# oldARK.net
KiCad netlist of a schematic drawn in EAGLE
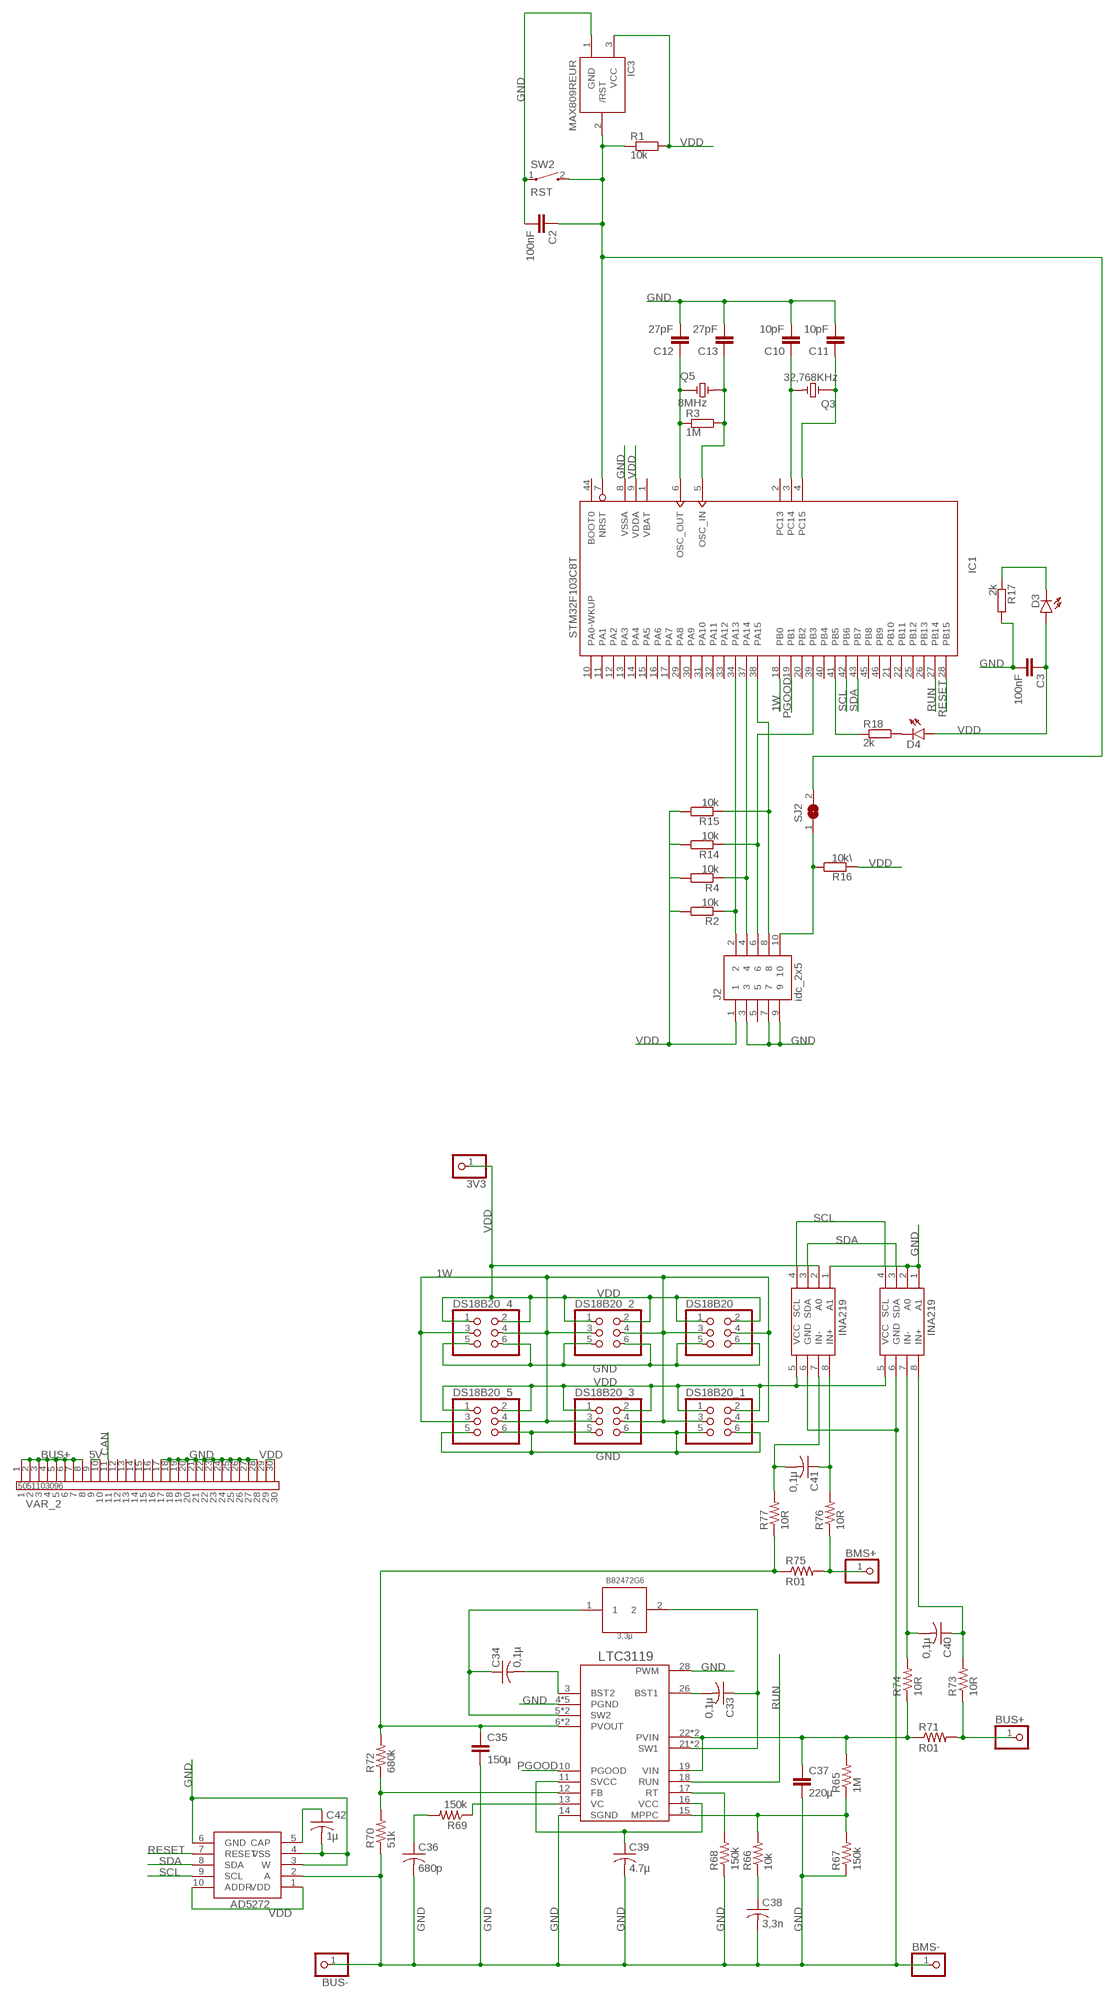
[diagram p0: schematic, sheet 1]

(export (version "E")
  (design (tool "Eeschema 10.0.6"))
  (components
    (comp (ref "3,3µH")
      (value "3,3µ")
      (footprint "eagle-import:B82472G6")
      (libsource (lib "eagle-import") (part "B82472G6"))
    )
    (comp (ref "3V3")
      (value "PINHD-1X1")
      (footprint "eagle-import:1X01")
      (libsource (lib "eagle-import") (part "PINHD-1X1"))
    )
    (comp (ref "BMS+")
      (value "PINHD-1X1")
      (footprint "eagle-import:1X01")
      (libsource (lib "eagle-import") (part "PINHD-1X1"))
    )
    (comp (ref "BMS-")
      (value "PINHD-1X1")
      (footprint "eagle-import:1X01")
      (libsource (lib "eagle-import") (part "PINHD-1X1"))
    )
    (comp (ref "BUS+")
      (value "PINHD-1X1")
      (footprint "eagle-import:1X01")
      (libsource (lib "eagle-import") (part "PINHD-1X1"))
    )
    (comp (ref "BUS-")
      (value "PINHD-1X1")
      (footprint "eagle-import:1X01")
      (libsource (lib "eagle-import") (part "PINHD-1X1"))
    )
    (comp (ref "C2")
      (value "100nF")
      (footprint "eagle-import:C0603")
      (libsource (lib "eagle-import") (part "C-EUC0603"))
    )
    (comp (ref "C3")
      (value "100nF")
      (footprint "eagle-import:C0603")
      (libsource (lib "eagle-import") (part "C-EUC0603"))
    )
    (comp (ref "C10")
      (value "10pF")
      (footprint "eagle-import:C0603")
      (libsource (lib "eagle-import") (part "C-EUC0603"))
    )
    (comp (ref "C11")
      (value "10pF")
      (footprint "eagle-import:C0603")
      (libsource (lib "eagle-import") (part "C-EUC0603"))
    )
    (comp (ref "C12")
      (value "27pF")
      (footprint "eagle-import:C0603")
      (libsource (lib "eagle-import") (part "C-EUC0603"))
    )
    (comp (ref "C13")
      (value "27pF")
      (footprint "eagle-import:C0603")
      (libsource (lib "eagle-import") (part "C-EUC0603"))
    )
    (comp (ref "C33")
      (value "0,1µ")
      (footprint "eagle-import:C0603")
      (libsource (lib "eagle-import") (part "C-USC0603"))
    )
    (comp (ref "C34")
      (value "0,1µ")
      (footprint "eagle-import:C0603")
      (libsource (lib "eagle-import") (part "C-USC0603"))
    )
    (comp (ref "C35")
      (value "150µ")
      (footprint "eagle-import:ECAP150")
      (libsource (lib "eagle-import") (part "ECAPECAP150"))
    )
    (comp (ref "C36")
      (value "680p")
      (footprint "eagle-import:C1206")
      (libsource (lib "eagle-import") (part "C-USC1206"))
    )
    (comp (ref "C37")
      (value "220µ")
      (footprint "eagle-import:ECAP220")
      (libsource (lib "eagle-import") (part "ECAPECAP220"))
    )
    (comp (ref "C38")
      (value "3,3n")
      (footprint "eagle-import:C1206")
      (libsource (lib "eagle-import") (part "C-USC1206"))
    )
    (comp (ref "C39")
      (value "4.7µ")
      (footprint "eagle-import:C1206")
      (libsource (lib "eagle-import") (part "C-USC1206"))
    )
    (comp (ref "C40")
      (value "0,1µ")
      (footprint "eagle-import:C0603")
      (libsource (lib "eagle-import") (part "C-USC0603"))
    )
    (comp (ref "C41")
      (value "0,1µ")
      (footprint "eagle-import:C0603")
      (libsource (lib "eagle-import") (part "C-USC0603"))
    )
    (comp (ref "C42")
      (value "1µ")
      (footprint "eagle-import:C0603")
      (libsource (lib "eagle-import") (part "C-USC0603"))
    )
    (comp (ref "D3")
      (value "HLMP6")
      (footprint "eagle-import:HLMP6")
      (fields (field (name "MF") "AGILENT TECHNOLOGIES") (field (name "MPN") "HLMP-6500"))
      (libsource (lib "eagle-import") (part "HLMP6"))
    )
    (comp (ref "D4")
      (value "HLMP6")
      (footprint "eagle-import:HLMP6")
      (fields (field (name "MF") "AGILENT TECHNOLOGIES") (field (name "MPN") "HLMP-6500"))
      (libsource (lib "eagle-import") (part "HLMP6"))
    )
    (comp (ref "DS18B20")
      (value "PINHD-2X3M")
      (footprint "eagle-import:2X03M")
      (libsource (lib "eagle-import") (part "PINHD-2X3M"))
    )
    (comp (ref "DS18B20_1")
      (value "PINHD-2X3M")
      (footprint "eagle-import:2X03M")
      (libsource (lib "eagle-import") (part "PINHD-2X3M"))
    )
    (comp (ref "DS18B20_2")
      (value "PINHD-2X3M")
      (footprint "eagle-import:2X03M")
      (libsource (lib "eagle-import") (part "PINHD-2X3M"))
    )
    (comp (ref "DS18B20_3")
      (value "PINHD-2X3M")
      (footprint "eagle-import:2X03M")
      (libsource (lib "eagle-import") (part "PINHD-2X3M"))
    )
    (comp (ref "DS18B20_4")
      (value "PINHD-2X3M")
      (footprint "eagle-import:2X03M")
      (libsource (lib "eagle-import") (part "PINHD-2X3M"))
    )
    (comp (ref "DS18B20_5")
      (value "PINHD-2X3M")
      (footprint "eagle-import:2X03M")
      (libsource (lib "eagle-import") (part "PINHD-2X3M"))
    )
    (comp (ref "IC1")
      (value "STM32F103C8T")
      (footprint "eagle-import:LQFP48")
      (libsource (lib "eagle-import") (part "STM32F103CT8"))
    )
    (comp (ref "IC3")
      (value "MAX809REUR")
      (footprint "eagle-import:SOT23")
      (fields (field (name "MF") "ON Semiconductor") (field (name "MP") "MAX809"))
      (libsource (lib "eagle-import") (part "MAX809EUR"))
    )
    (comp (ref "J2")
      (value "idc_2x5")
      (footprint "eagle-import:CNC_3221-10-0100-00")
      (fields (field (name "MF") "CNC Tech") (field (name "MP") "3221-10-0100-00"))
      (libsource (lib "eagle-import") (part "3221-10-0100-00"))
    )
    (comp (ref "Q3")
      (value "32,768KHz")
      (footprint "eagle-import:XTAL_9C-8.000MEEJ-T")
      (fields (field (name "MF") "TXC CORPORATION") (field (name "MP") "9C-8.000MEEJ-T"))
      (libsource (lib "eagle-import") (part "9C-8.000MEEJ-T"))
    )
    (comp (ref "Q5")
      (value "8MHz")
      (footprint "eagle-import:XTAL_9C-8.000MEEJ-T")
      (fields (field (name "MF") "TXC CORPORATION") (field (name "MP") "9C-8.000MEEJ-T"))
      (libsource (lib "eagle-import") (part "9C-8.000MEEJ-T"))
    )
    (comp (ref "R1")
      (value "10k")
      (footprint "eagle-import:BVS")
      (libsource (lib "eagle-import") (part "BVS"))
    )
    (comp (ref "R2")
      (value "10k")
      (footprint "eagle-import:BVS")
      (libsource (lib "eagle-import") (part "BVS"))
    )
    (comp (ref "R3")
      (value "1M")
      (footprint "eagle-import:BVS")
      (libsource (lib "eagle-import") (part "BVS"))
    )
    (comp (ref "R4")
      (value "10k")
      (footprint "eagle-import:BVS")
      (libsource (lib "eagle-import") (part "BVS"))
    )
    (comp (ref "R14")
      (value "10k")
      (footprint "eagle-import:BVS")
      (libsource (lib "eagle-import") (part "BVS"))
    )
    (comp (ref "R15")
      (value "10k")
      (footprint "eagle-import:BVS")
      (libsource (lib "eagle-import") (part "BVS"))
    )
    (comp (ref "R16")
      (value "10k\\")
      (footprint "eagle-import:BVS")
      (libsource (lib "eagle-import") (part "BVS"))
    )
    (comp (ref "R17")
      (value "2k")
      (footprint "eagle-import:BVS")
      (libsource (lib "eagle-import") (part "BVS"))
    )
    (comp (ref "R18")
      (value "2k")
      (footprint "eagle-import:BVS")
      (libsource (lib "eagle-import") (part "BVS"))
    )
    (comp (ref "R65")
      (value "1M")
      (footprint "eagle-import:R0603")
      (libsource (lib "eagle-import") (part "resistor_348_R-US_R0603"))
    )
    (comp (ref "R66")
      (value "10k")
      (footprint "eagle-import:R0603")
      (libsource (lib "eagle-import") (part "resistor_348_R-US_R0603"))
    )
    (comp (ref "R67")
      (value "150k")
      (footprint "eagle-import:R0603")
      (libsource (lib "eagle-import") (part "resistor_348_R-US_R0603"))
    )
    (comp (ref "R68")
      (value "150k")
      (footprint "eagle-import:R0603")
      (libsource (lib "eagle-import") (part "resistor_348_R-US_R0603"))
    )
    (comp (ref "R69")
      (value "150k")
      (footprint "eagle-import:R0603")
      (libsource (lib "eagle-import") (part "resistor_348_R-US_R0603"))
    )
    (comp (ref "R70")
      (value "51k")
      (footprint "eagle-import:R0603")
      (libsource (lib "eagle-import") (part "resistor_348_R-US_R0603"))
    )
    (comp (ref "R71")
      (value "R01")
      (footprint "eagle-import:R2512")
      (libsource (lib "eagle-import") (part "R-US_R2512"))
    )
    (comp (ref "R72")
      (value "680k")
      (footprint "eagle-import:R0603")
      (libsource (lib "eagle-import") (part "resistor_348_R-US_R0603"))
    )
    (comp (ref "R73")
      (value "10R")
      (footprint "eagle-import:R0603")
      (libsource (lib "eagle-import") (part "resistor_348_R-US_R0603"))
    )
    (comp (ref "R74")
      (value "10R")
      (footprint "eagle-import:R0603")
      (libsource (lib "eagle-import") (part "resistor_348_R-US_R0603"))
    )
    (comp (ref "R75")
      (value "R01")
      (footprint "eagle-import:R2512")
      (libsource (lib "eagle-import") (part "R-US_R2512"))
    )
    (comp (ref "R76")
      (value "10R")
      (footprint "eagle-import:R0603")
      (libsource (lib "eagle-import") (part "resistor_348_R-US_R0603"))
    )
    (comp (ref "R77")
      (value "10R")
      (footprint "eagle-import:R0603")
      (libsource (lib "eagle-import") (part "resistor_348_R-US_R0603"))
    )
    (comp (ref "SJ2")
      (value "SJW")
      (footprint "eagle-import:SJW")
      (libsource (lib "eagle-import") (part "SJW"))
    )
    (comp (ref "SW2")
      (value "RST")
      (footprint "eagle-import:SW_1437566-3")
      (fields (field (name "COMMENT") "1437566-3") (field (name "MF") "TE Connectivity"))
      (libsource (lib "eagle-import") (part "1437566-3"))
    )
    (comp (ref "U$4")
      (value "5051103096")
      (footprint "eagle-import:5051103096")
      (libsource (lib "eagle-import") (part "5051103096"))
    )
    (comp (ref "U$57")
      (value "INA219AID")
      (footprint "eagle-import:INA219AID")
      (libsource (lib "eagle-import") (part "INA219AID"))
    )
    (comp (ref "U$58")
      (value "INA219AID")
      (footprint "eagle-import:INA219AID")
      (libsource (lib "eagle-import") (part "INA219AID"))
    )
    (comp (ref "U$59")
      (value "LTC3119")
      (footprint "eagle-import:LTC3119")
      (libsource (lib "eagle-import") (part "LTC3119"))
    )
    (comp (ref "U$60")
      (value "AD5272")
      (footprint "eagle-import:AD5272")
      (libsource (lib "eagle-import") (part "AD5272"))
    )
  )
  (nets
    (net (code "1") (name "/1W") (class "Default")
      (node (ref "DS18B20") (pin "3") (pinfunction "3_3") (pintype "passive"))
      (node (ref "DS18B20") (pin "4") (pinfunction "4_4") (pintype "passive"))
      (node (ref "DS18B20_1") (pin "3") (pinfunction "3_3") (pintype "passive"))
      (node (ref "DS18B20_1") (pin "4") (pinfunction "4_4") (pintype "passive"))
      (node (ref "DS18B20_2") (pin "3") (pinfunction "3_3") (pintype "passive"))
      (node (ref "DS18B20_2") (pin "4") (pinfunction "4_4") (pintype "passive"))
      (node (ref "DS18B20_3") (pin "3") (pinfunction "3_3") (pintype "passive"))
      (node (ref "DS18B20_3") (pin "4") (pinfunction "4_4") (pintype "passive"))
      (node (ref "DS18B20_4") (pin "3") (pinfunction "3_3") (pintype "passive"))
      (node (ref "DS18B20_4") (pin "4") (pinfunction "4_4") (pintype "passive"))
      (node (ref "DS18B20_5") (pin "3") (pinfunction "3_3") (pintype "passive"))
      (node (ref "DS18B20_5") (pin "4") (pinfunction "4_4") (pintype "passive"))
      (node (ref "IC1") (pin "18") (pinfunction "PB0_18") (pintype "bidirectional"))
    )
    (net (code "2") (name "/5V") (class "Default")
      (node (ref "U$4") (pin "10") (pinfunction "10_10") (pintype "bidirectional"))
      (node (ref "U$4") (pin "9") (pinfunction "9_9") (pintype "bidirectional"))
    )
    (net (code "3") (name "/BUS+") (class "Default")
      (node (ref "U$4") (pin "1") (pinfunction "1_1") (pintype "bidirectional"))
      (node (ref "U$4") (pin "2") (pinfunction "2_2") (pintype "bidirectional"))
      (node (ref "U$4") (pin "3") (pinfunction "3_3") (pintype "bidirectional"))
      (node (ref "U$4") (pin "4") (pinfunction "4_4") (pintype "bidirectional"))
      (node (ref "U$4") (pin "5") (pinfunction "5_5") (pintype "bidirectional"))
      (node (ref "U$4") (pin "6") (pinfunction "6_6") (pintype "bidirectional"))
      (node (ref "U$4") (pin "7") (pinfunction "7_7") (pintype "bidirectional"))
      (node (ref "U$4") (pin "8") (pinfunction "8_8") (pintype "bidirectional"))
    )
    (net (code "5") (name "/GND") (class "Default")
      (node (ref "BMS-") (pin "1") (pinfunction "1_1") (pintype "passive"))
      (node (ref "BUS-") (pin "1") (pinfunction "1_1") (pintype "passive"))
      (node (ref "C10") (pin "2") (pinfunction "2_2") (pintype "passive"))
      (node (ref "C11") (pin "2") (pinfunction "2_2") (pintype "passive"))
      (node (ref "C12") (pin "2") (pinfunction "2_2") (pintype "passive"))
      (node (ref "C13") (pin "2") (pinfunction "2_2") (pintype "passive"))
      (node (ref "C2") (pin "2") (pinfunction "2_2") (pintype "passive"))
      (node (ref "C3") (pin "2") (pinfunction "2_2") (pintype "passive"))
      (node (ref "C35") (pin "P$2") (pinfunction "2_P$2") (pintype "passive"))
      (node (ref "C36") (pin "2") (pinfunction "2_2") (pintype "passive"))
      (node (ref "C37") (pin "P$2") (pinfunction "2_P$2") (pintype "passive"))
      (node (ref "C38") (pin "2") (pinfunction "2_2") (pintype "passive"))
      (node (ref "C39") (pin "2") (pinfunction "2_2") (pintype "passive"))
      (node (ref "C42") (pin "2") (pinfunction "2_2") (pintype "passive"))
      (node (ref "DS18B20") (pin "5") (pinfunction "5_5") (pintype "passive"))
      (node (ref "DS18B20") (pin "6") (pinfunction "6_6") (pintype "passive"))
      (node (ref "DS18B20_1") (pin "5") (pinfunction "5_5") (pintype "passive"))
      (node (ref "DS18B20_1") (pin "6") (pinfunction "6_6") (pintype "passive"))
      (node (ref "DS18B20_2") (pin "5") (pinfunction "5_5") (pintype "passive"))
      (node (ref "DS18B20_2") (pin "6") (pinfunction "6_6") (pintype "passive"))
      (node (ref "DS18B20_3") (pin "5") (pinfunction "5_5") (pintype "passive"))
      (node (ref "DS18B20_3") (pin "6") (pinfunction "6_6") (pintype "passive"))
      (node (ref "DS18B20_4") (pin "5") (pinfunction "5_5") (pintype "passive"))
      (node (ref "DS18B20_4") (pin "6") (pinfunction "6_6") (pintype "passive"))
      (node (ref "DS18B20_5") (pin "5") (pinfunction "5_5") (pintype "passive"))
      (node (ref "DS18B20_5") (pin "6") (pinfunction "6_6") (pintype "passive"))
      (node (ref "IC1") (pin "8") (pinfunction "VSSA_8") (pintype "power_in"))
      (node (ref "IC3") (pin "1") (pinfunction "GND_1") (pintype "power_in"))
      (node (ref "J2") (pin "3") (pinfunction "3_3") (pintype "passive"))
      (node (ref "J2") (pin "7") (pinfunction "7_7") (pintype "passive"))
      (node (ref "J2") (pin "9") (pinfunction "9_9") (pintype "passive"))
      (node (ref "R17") (pin "1") (pinfunction "1_1") (pintype "passive"))
      (node (ref "R67") (pin "1") (pinfunction "1_1") (pintype "passive"))
      (node (ref "R68") (pin "1") (pinfunction "1_1") (pintype "passive"))
      (node (ref "R70") (pin "1") (pinfunction "1_1") (pintype "passive"))
      (node (ref "SW2") (pin "1") (pinfunction "1_1") (pintype "passive"))
      (node (ref "U$4") (pin "17") (pinfunction "17_17") (pintype "bidirectional"))
      (node (ref "U$4") (pin "18") (pinfunction "18_18") (pintype "bidirectional"))
      (node (ref "U$4") (pin "19") (pinfunction "19_19") (pintype "bidirectional"))
      (node (ref "U$4") (pin "20") (pinfunction "20_20") (pintype "bidirectional"))
      (node (ref "U$4") (pin "21") (pinfunction "21_21") (pintype "bidirectional"))
      (node (ref "U$4") (pin "22") (pinfunction "22_22") (pintype "bidirectional"))
      (node (ref "U$4") (pin "23") (pinfunction "23_23") (pintype "bidirectional"))
      (node (ref "U$4") (pin "24") (pinfunction "24_24") (pintype "bidirectional"))
      (node (ref "U$4") (pin "25") (pinfunction "25_25") (pintype "bidirectional"))
      (node (ref "U$4") (pin "26") (pinfunction "26_26") (pintype "bidirectional"))
      (node (ref "U$4") (pin "27") (pinfunction "27_27") (pintype "bidirectional"))
      (node (ref "U$4") (pin "28") (pinfunction "28_28") (pintype "bidirectional"))
      (node (ref "U$57") (pin "1") (pinfunction "A1_1") (pintype "bidirectional"))
      (node (ref "U$57") (pin "6") (pinfunction "GND_6") (pintype "bidirectional"))
      (node (ref "U$58") (pin "1") (pinfunction "A1_1") (pintype "bidirectional"))
      (node (ref "U$58") (pin "2") (pinfunction "A0_2") (pintype "bidirectional"))
      (node (ref "U$58") (pin "6") (pinfunction "GND_6") (pintype "bidirectional"))
      (node (ref "U$59") (pin "14") (pinfunction "SGND_14") (pintype "bidirectional"))
      (node (ref "U$59") (pin "20") (pinfunction "PGND_20") (pintype "bidirectional"))
      (node (ref "U$59") (pin "25") (pinfunction "PGND_25") (pintype "bidirectional"))
      (node (ref "U$59") (pin "28") (pinfunction "PWM_28") (pintype "bidirectional"))
      (node (ref "U$59") (pin "29") (pinfunction "PGND_29") (pintype "bidirectional"))
      (node (ref "U$59") (pin "4") (pinfunction "PGND_4") (pintype "bidirectional"))
      (node (ref "U$59") (pin "9") (pinfunction "PGND_9") (pintype "bidirectional"))
      (node (ref "U$60") (pin "2") (pinfunction "A_2") (pintype "bidirectional"))
      (node (ref "U$60") (pin "3") (pinfunction "W_3") (pintype "bidirectional"))
      (node (ref "U$60") (pin "4") (pinfunction "VSS_4") (pintype "bidirectional"))
      (node (ref "U$60") (pin "6") (pinfunction "GND_6") (pintype "bidirectional"))
    )
    (net (code "6") (name "/PGOOD") (class "Default")
      (node (ref "IC1") (pin "19") (pinfunction "PB1_19") (pintype "bidirectional"))
      (node (ref "U$59") (pin "10") (pinfunction "PGOOD_10") (pintype "bidirectional"))
    )
    (net (code "7") (name "/RESET") (class "Default")
      (node (ref "IC1") (pin "28") (pinfunction "PB15_28") (pintype "bidirectional"))
      (node (ref "U$60") (pin "7") (pinfunction "RESET_7") (pintype "bidirectional"))
    )
    (net (code "8") (name "/RUN") (class "Default")
      (node (ref "IC1") (pin "27") (pinfunction "PB14_27") (pintype "bidirectional"))
      (node (ref "U$59") (pin "18") (pinfunction "RUN_18") (pintype "bidirectional"))
    )
    (net (code "9") (name "/SCL") (class "Default")
      (node (ref "IC1") (pin "42") (pinfunction "PB6_42") (pintype "bidirectional"))
      (node (ref "U$57") (pin "4") (pinfunction "SCL_4") (pintype "bidirectional"))
      (node (ref "U$58") (pin "4") (pinfunction "SCL_4") (pintype "bidirectional"))
      (node (ref "U$60") (pin "9") (pinfunction "SCL_9") (pintype "bidirectional"))
    )
    (net (code "10") (name "/SDA") (class "Default")
      (node (ref "IC1") (pin "43") (pinfunction "PB7_43") (pintype "bidirectional"))
      (node (ref "U$57") (pin "3") (pinfunction "SDA_3") (pintype "bidirectional"))
      (node (ref "U$58") (pin "3") (pinfunction "SDA_3") (pintype "bidirectional"))
      (node (ref "U$60") (pin "8") (pinfunction "SDA_8") (pintype "bidirectional"))
    )
    (net (code "11") (name "/VBAT") (class "Default")
      (node (ref "IC1") (pin "1") (pinfunction "VBAT_1") (pintype "power_in"))
    )
    (net (code "12") (name "/VDD") (class "Default")
      (node (ref "3V3") (pin "1") (pinfunction "1_1") (pintype "passive"))
      (node (ref "C3") (pin "1") (pinfunction "1_1") (pintype "passive"))
      (node (ref "D3") (pin "A") (pinfunction "A_A") (pintype "passive"))
      (node (ref "D4") (pin "A") (pinfunction "A_A") (pintype "passive"))
      (node (ref "DS18B20") (pin "1") (pinfunction "1_1") (pintype "passive"))
      (node (ref "DS18B20") (pin "2") (pinfunction "2_2") (pintype "passive"))
      (node (ref "DS18B20_1") (pin "1") (pinfunction "1_1") (pintype "passive"))
      (node (ref "DS18B20_1") (pin "2") (pinfunction "2_2") (pintype "passive"))
      (node (ref "DS18B20_2") (pin "1") (pinfunction "1_1") (pintype "passive"))
      (node (ref "DS18B20_2") (pin "2") (pinfunction "2_2") (pintype "passive"))
      (node (ref "DS18B20_3") (pin "1") (pinfunction "1_1") (pintype "passive"))
      (node (ref "DS18B20_3") (pin "2") (pinfunction "2_2") (pintype "passive"))
      (node (ref "DS18B20_4") (pin "1") (pinfunction "1_1") (pintype "passive"))
      (node (ref "DS18B20_4") (pin "2") (pinfunction "2_2") (pintype "passive"))
      (node (ref "DS18B20_5") (pin "1") (pinfunction "1_1") (pintype "passive"))
      (node (ref "DS18B20_5") (pin "2") (pinfunction "2_2") (pintype "passive"))
      (node (ref "IC1") (pin "9") (pinfunction "VDDA_9") (pintype "power_in"))
      (node (ref "IC3") (pin "3") (pinfunction "VCC_3") (pintype "input"))
      (node (ref "J2") (pin "1") (pinfunction "1_1") (pintype "passive"))
      (node (ref "R1") (pin "1") (pinfunction "1_1") (pintype "passive"))
      (node (ref "R14") (pin "1") (pinfunction "1_1") (pintype "passive"))
      (node (ref "R15") (pin "1") (pinfunction "1_1") (pintype "passive"))
      (node (ref "R16") (pin "2") (pinfunction "2_2") (pintype "passive"))
      (node (ref "R2") (pin "1") (pinfunction "1_1") (pintype "passive"))
      (node (ref "R4") (pin "1") (pinfunction "1_1") (pintype "passive"))
      (node (ref "U$4") (pin "29") (pinfunction "29_29") (pintype "bidirectional"))
      (node (ref "U$4") (pin "30") (pinfunction "30_30") (pintype "bidirectional"))
      (node (ref "U$57") (pin "2") (pinfunction "A0_2") (pintype "bidirectional"))
      (node (ref "U$57") (pin "5") (pinfunction "VCC_5") (pintype "bidirectional"))
      (node (ref "U$58") (pin "5") (pinfunction "VCC_5") (pintype "bidirectional"))
      (node (ref "U$60") (pin "1") (pinfunction "VDD_1") (pintype "bidirectional"))
      (node (ref "U$60") (pin "10") (pinfunction "ADDR_10") (pintype "bidirectional"))
    )
    (net (code "13") (name "Net-(3,3µH-Pad1)") (class "Default")
      (node (ref "3,3µH") (pin "1") (pinfunction "1_1") (pintype "bidirectional"))
      (node (ref "C34") (pin "1") (pinfunction "1_1") (pintype "passive"))
      (node (ref "U$59") (pin "5") (pinfunction "SW2_5") (pintype "bidirectional"))
      (node (ref "U$59") (pin "8") (pinfunction "SW2_8") (pintype "bidirectional"))
    )
    (net (code "14") (name "Net-(3,3µH-Pad2)") (class "Default")
      (node (ref "3,3µH") (pin "2") (pinfunction "2_2") (pintype "bidirectional"))
      (node (ref "C33") (pin "1") (pinfunction "1_1") (pintype "passive"))
      (node (ref "U$59") (pin "21") (pinfunction "SW1_21") (pintype "bidirectional"))
      (node (ref "U$59") (pin "24") (pinfunction "SW1_24") (pintype "bidirectional"))
    )
    (net (code "15") (name "Net-(BMS+-Pad1)") (class "Default")
      (node (ref "BMS+") (pin "1") (pinfunction "1_1") (pintype "passive"))
      (node (ref "R75") (pin "2") (pinfunction "2_2") (pintype "passive"))
      (node (ref "R76") (pin "1") (pinfunction "1_1") (pintype "passive"))
    )
    (net (code "16") (name "Net-(BUS+-Pad1)") (class "Default")
      (node (ref "BUS+") (pin "1") (pinfunction "1_1") (pintype "passive"))
      (node (ref "R71") (pin "2") (pinfunction "2_2") (pintype "passive"))
      (node (ref "R73") (pin "1") (pinfunction "1_1") (pintype "passive"))
    )
    (net (code "17") (name "Net-(C35-1)") (class "Default")
      (node (ref "C35") (pin "P$1") (pinfunction "1_P$1") (pintype "passive"))
      (node (ref "R72") (pin "2") (pinfunction "2_2") (pintype "passive"))
      (node (ref "R75") (pin "1") (pinfunction "1_1") (pintype "passive"))
      (node (ref "R77") (pin "1") (pinfunction "1_1") (pintype "passive"))
      (node (ref "U$59") (pin "6") (pinfunction "PVOUT_6") (pintype "bidirectional"))
      (node (ref "U$59") (pin "7") (pinfunction "PVOUT_7") (pintype "bidirectional"))
    )
    (net (code "18") (name "Net-(C36-Pad1)") (class "Default")
      (node (ref "C36") (pin "1") (pinfunction "1_1") (pintype "passive"))
      (node (ref "R69") (pin "2") (pinfunction "2_2") (pintype "passive"))
    )
    (net (code "19") (name "Net-(C37-1)") (class "Default")
      (node (ref "C37") (pin "P$1") (pinfunction "1_P$1") (pintype "passive"))
      (node (ref "R65") (pin "2") (pinfunction "2_2") (pintype "passive"))
      (node (ref "R71") (pin "1") (pinfunction "1_1") (pintype "passive"))
      (node (ref "R74") (pin "1") (pinfunction "1_1") (pintype "passive"))
      (node (ref "U$59") (pin "19") (pinfunction "VIN_19") (pintype "bidirectional"))
      (node (ref "U$59") (pin "22") (pinfunction "PVIN_22") (pintype "bidirectional"))
      (node (ref "U$59") (pin "23") (pinfunction "PVIN_23") (pintype "bidirectional"))
    )
    (net (code "20") (name "Net-(C38-Pad1)") (class "Default")
      (node (ref "C38") (pin "1") (pinfunction "1_1") (pintype "passive"))
      (node (ref "R66") (pin "1") (pinfunction "1_1") (pintype "passive"))
    )
    (net (code "21") (name "Net-(D3-PadK)") (class "Default")
      (node (ref "D3") (pin "K") (pinfunction "K_K") (pintype "passive"))
      (node (ref "R17") (pin "2") (pinfunction "2_2") (pintype "passive"))
    )
    (net (code "22") (name "Net-(D4-PadK)") (class "Default")
      (node (ref "D4") (pin "K") (pinfunction "K_K") (pintype "passive"))
      (node (ref "R18") (pin "1") (pinfunction "1_1") (pintype "passive"))
    )
    (net (code "23") (name "Net-(IC1A-NRST)") (class "Default")
      (node (ref "C2") (pin "1") (pinfunction "1_1") (pintype "passive"))
      (node (ref "IC1") (pin "7") (pinfunction "NRST_7") (pintype "bidirectional"))
      (node (ref "IC3") (pin "2") (pinfunction "/RST_2") (pintype "output"))
      (node (ref "R1") (pin "2") (pinfunction "2_2") (pintype "passive"))
      (node (ref "SJ2") (pin "2") (pinfunction "2_2") (pintype "passive"))
      (node (ref "SW2") (pin "2") (pinfunction "2_2") (pintype "passive"))
    )
    (net (code "24") (name "Net-(IC1A-OSC_IN)") (class "Default")
      (node (ref "C13") (pin "1") (pinfunction "1_1") (pintype "passive"))
      (node (ref "IC1") (pin "5") (pinfunction "OSC_IN_5") (pintype "bidirectional"))
      (node (ref "Q5") (pin "2") (pinfunction "2_2") (pintype "passive"))
      (node (ref "R3") (pin "1") (pinfunction "1_1") (pintype "passive"))
    )
    (net (code "25") (name "Net-(IC1A-OSC_OUT)") (class "Default")
      (node (ref "C12") (pin "1") (pinfunction "1_1") (pintype "passive"))
      (node (ref "IC1") (pin "6") (pinfunction "OSC_OUT_6") (pintype "bidirectional"))
      (node (ref "Q5") (pin "1") (pinfunction "1_1") (pintype "passive"))
      (node (ref "R3") (pin "2") (pinfunction "2_2") (pintype "passive"))
    )
    (net (code "26") (name "Net-(IC1A-PA13)") (class "Default")
      (node (ref "IC1") (pin "34") (pinfunction "PA13_34") (pintype "bidirectional"))
      (node (ref "J2") (pin "2") (pinfunction "2_2") (pintype "passive"))
      (node (ref "R2") (pin "2") (pinfunction "2_2") (pintype "passive"))
    )
    (net (code "27") (name "Net-(IC1A-PA14)") (class "Default")
      (node (ref "IC1") (pin "37") (pinfunction "PA14_37") (pintype "bidirectional"))
      (node (ref "J2") (pin "4") (pinfunction "4_4") (pintype "passive"))
      (node (ref "R4") (pin "2") (pinfunction "2_2") (pintype "passive"))
    )
    (net (code "28") (name "Net-(IC1A-PA15)") (class "Default")
      (node (ref "IC1") (pin "38") (pinfunction "PA15_38") (pintype "bidirectional"))
      (node (ref "J2") (pin "8") (pinfunction "8_8") (pintype "passive"))
      (node (ref "R15") (pin "2") (pinfunction "2_2") (pintype "passive"))
    )
    (net (code "29") (name "Net-(IC1A-PB3)") (class "Default")
      (node (ref "IC1") (pin "39") (pinfunction "PB3_39") (pintype "bidirectional"))
      (node (ref "J2") (pin "6") (pinfunction "6_6") (pintype "passive"))
      (node (ref "R14") (pin "2") (pinfunction "2_2") (pintype "passive"))
    )
    (net (code "30") (name "Net-(IC1A-PB5)") (class "Default")
      (node (ref "IC1") (pin "41") (pinfunction "PB5_41") (pintype "bidirectional"))
      (node (ref "R18") (pin "2") (pinfunction "2_2") (pintype "passive"))
    )
    (net (code "31") (name "Net-(IC1A-PC14)") (class "Default")
      (node (ref "C10") (pin "1") (pinfunction "1_1") (pintype "passive"))
      (node (ref "IC1") (pin "3") (pinfunction "PC14_3") (pintype "bidirectional"))
      (node (ref "Q3") (pin "2") (pinfunction "2_2") (pintype "passive"))
    )
    (net (code "32") (name "Net-(IC1A-PC15)") (class "Default")
      (node (ref "C11") (pin "1") (pinfunction "1_1") (pintype "passive"))
      (node (ref "IC1") (pin "4") (pinfunction "PC15_4") (pintype "bidirectional"))
      (node (ref "Q3") (pin "1") (pinfunction "1_1") (pintype "passive"))
    )
    (net (code "33") (name "Net-(J2-Pad10)") (class "Default")
      (node (ref "J2") (pin "10") (pinfunction "10_10") (pintype "passive"))
      (node (ref "R16") (pin "1") (pinfunction "1_1") (pintype "passive"))
      (node (ref "SJ2") (pin "1") (pinfunction "1_1") (pintype "passive"))
    )
    (net (code "34") (name "Net-(U$57-IN+)") (class "Default")
      (node (ref "C41") (pin "1") (pinfunction "1_1") (pintype "passive"))
      (node (ref "R76") (pin "2") (pinfunction "2_2") (pintype "passive"))
      (node (ref "U$57") (pin "8") (pinfunction "IN+_8") (pintype "bidirectional"))
    )
    (net (code "35") (name "Net-(U$57-IN-)") (class "Default")
      (node (ref "C41") (pin "2") (pinfunction "2_2") (pintype "passive"))
      (node (ref "R77") (pin "2") (pinfunction "2_2") (pintype "passive"))
      (node (ref "U$57") (pin "7") (pinfunction "IN-_7") (pintype "bidirectional"))
    )
    (net (code "36") (name "Net-(U$58-IN+)") (class "Default")
      (node (ref "C40") (pin "1") (pinfunction "1_1") (pintype "passive"))
      (node (ref "R73") (pin "2") (pinfunction "2_2") (pintype "passive"))
      (node (ref "U$58") (pin "8") (pinfunction "IN+_8") (pintype "bidirectional"))
    )
    (net (code "37") (name "Net-(U$58-IN-)") (class "Default")
      (node (ref "C40") (pin "2") (pinfunction "2_2") (pintype "passive"))
      (node (ref "R74") (pin "2") (pinfunction "2_2") (pintype "passive"))
      (node (ref "U$58") (pin "7") (pinfunction "IN-_7") (pintype "bidirectional"))
    )
    (net (code "38") (name "Net-(U$59-BST1)") (class "Default")
      (node (ref "C33") (pin "2") (pinfunction "2_2") (pintype "passive"))
      (node (ref "U$59") (pin "26") (pinfunction "BST1_26") (pintype "bidirectional"))
    )
    (net (code "39") (name "Net-(U$59-BST2)") (class "Default")
      (node (ref "C34") (pin "2") (pinfunction "2_2") (pintype "passive"))
      (node (ref "U$59") (pin "3") (pinfunction "BST2_3") (pintype "bidirectional"))
    )
    (net (code "40") (name "Net-(U$59-FB)") (class "Default")
      (node (ref "R70") (pin "2") (pinfunction "2_2") (pintype "passive"))
      (node (ref "R72") (pin "1") (pinfunction "1_1") (pintype "passive"))
      (node (ref "U$59") (pin "12") (pinfunction "FB_12") (pintype "bidirectional"))
    )
    (net (code "41") (name "Net-(U$59-MPPC)") (class "Default")
      (node (ref "R65") (pin "1") (pinfunction "1_1") (pintype "passive"))
      (node (ref "R66") (pin "2") (pinfunction "2_2") (pintype "passive"))
      (node (ref "R67") (pin "2") (pinfunction "2_2") (pintype "passive"))
      (node (ref "U$59") (pin "15") (pinfunction "MPPC_15") (pintype "bidirectional"))
    )
    (net (code "42") (name "Net-(U$59-RT)") (class "Default")
      (node (ref "R68") (pin "2") (pinfunction "2_2") (pintype "passive"))
      (node (ref "U$59") (pin "17") (pinfunction "RT_17") (pintype "bidirectional"))
    )
    (net (code "43") (name "Net-(U$59-SVCC)") (class "Default")
      (node (ref "C39") (pin "1") (pinfunction "1_1") (pintype "passive"))
      (node (ref "U$59") (pin "11") (pinfunction "SVCC_11") (pintype "bidirectional"))
      (node (ref "U$59") (pin "16") (pinfunction "VCC_16") (pintype "bidirectional"))
    )
    (net (code "44") (name "Net-(U$59-VC)") (class "Default")
      (node (ref "R69") (pin "1") (pinfunction "1_1") (pintype "passive"))
      (node (ref "U$59") (pin "13") (pinfunction "VC_13") (pintype "bidirectional"))
    )
    (net (code "45") (name "Net-(U$60-CAP)") (class "Default")
      (node (ref "C42") (pin "1") (pinfunction "1_1") (pintype "passive"))
      (node (ref "U$60") (pin "5") (pinfunction "CAP_5") (pintype "bidirectional"))
    )
    (net (code "46") (name "unconnected-(IC1A-BOOT0-Pad44)") (class "Default")
      (node (ref "IC1") (pin "44") (pinfunction "BOOT0_44") (pintype "input"))
    )
    (net (code "47") (name "unconnected-(IC1A-PA0-WKUP-Pad10)") (class "Default")
      (node (ref "IC1") (pin "10") (pinfunction "PA0-WKUP_10") (pintype "bidirectional"))
    )
    (net (code "48") (name "unconnected-(IC1A-PA1-Pad11)") (class "Default")
      (node (ref "IC1") (pin "11") (pinfunction "PA1_11") (pintype "bidirectional"))
    )
    (net (code "49") (name "unconnected-(IC1A-PA2-Pad12)") (class "Default")
      (node (ref "IC1") (pin "12") (pinfunction "PA2_12") (pintype "bidirectional"))
    )
    (net (code "50") (name "unconnected-(IC1A-PA3-Pad13)") (class "Default")
      (node (ref "IC1") (pin "13") (pinfunction "PA3_13") (pintype "bidirectional"))
    )
    (net (code "51") (name "unconnected-(IC1A-PA4-Pad14)") (class "Default")
      (node (ref "IC1") (pin "14") (pinfunction "PA4_14") (pintype "bidirectional"))
    )
    (net (code "52") (name "unconnected-(IC1A-PA5-Pad15)") (class "Default")
      (node (ref "IC1") (pin "15") (pinfunction "PA5_15") (pintype "bidirectional"))
    )
    (net (code "53") (name "unconnected-(IC1A-PA6-Pad16)") (class "Default")
      (node (ref "IC1") (pin "16") (pinfunction "PA6_16") (pintype "bidirectional"))
    )
    (net (code "54") (name "unconnected-(IC1A-PA7-Pad17)") (class "Default")
      (node (ref "IC1") (pin "17") (pinfunction "PA7_17") (pintype "bidirectional"))
    )
    (net (code "55") (name "unconnected-(IC1A-PA8-Pad29)") (class "Default")
      (node (ref "IC1") (pin "29") (pinfunction "PA8_29") (pintype "bidirectional"))
    )
    (net (code "56") (name "unconnected-(IC1A-PA9-Pad30)") (class "Default")
      (node (ref "IC1") (pin "30") (pinfunction "PA9_30") (pintype "bidirectional"))
    )
    (net (code "57") (name "unconnected-(IC1A-PA10-Pad31)") (class "Default")
      (node (ref "IC1") (pin "31") (pinfunction "PA10_31") (pintype "bidirectional"))
    )
    (net (code "58") (name "unconnected-(IC1A-PA11-Pad32)") (class "Default")
      (node (ref "IC1") (pin "32") (pinfunction "PA11_32") (pintype "bidirectional"))
    )
    (net (code "59") (name "unconnected-(IC1A-PA12-Pad33)") (class "Default")
      (node (ref "IC1") (pin "33") (pinfunction "PA12_33") (pintype "bidirectional"))
    )
    (net (code "60") (name "unconnected-(IC1A-PB2-Pad20)") (class "Default")
      (node (ref "IC1") (pin "20") (pinfunction "PB2_20") (pintype "bidirectional"))
    )
    (net (code "61") (name "unconnected-(IC1A-PB4-Pad40)") (class "Default")
      (node (ref "IC1") (pin "40") (pinfunction "PB4_40") (pintype "bidirectional"))
    )
    (net (code "62") (name "unconnected-(IC1A-PB8-Pad45)") (class "Default")
      (node (ref "IC1") (pin "45") (pinfunction "PB8_45") (pintype "bidirectional"))
    )
    (net (code "63") (name "unconnected-(IC1A-PB9-Pad46)") (class "Default")
      (node (ref "IC1") (pin "46") (pinfunction "PB9_46") (pintype "bidirectional"))
    )
    (net (code "64") (name "unconnected-(IC1A-PB10-Pad21)") (class "Default")
      (node (ref "IC1") (pin "21") (pinfunction "PB10_21") (pintype "bidirectional"))
    )
    (net (code "65") (name "unconnected-(IC1A-PB11-Pad22)") (class "Default")
      (node (ref "IC1") (pin "22") (pinfunction "PB11_22") (pintype "bidirectional"))
    )
    (net (code "66") (name "unconnected-(IC1A-PB12-Pad25)") (class "Default")
      (node (ref "IC1") (pin "25") (pinfunction "PB12_25") (pintype "bidirectional"))
    )
    (net (code "67") (name "unconnected-(IC1A-PB13-Pad26)") (class "Default")
      (node (ref "IC1") (pin "26") (pinfunction "PB13_26") (pintype "bidirectional"))
    )
    (net (code "68") (name "unconnected-(IC1A-PC13-Pad2)") (class "Default")
      (node (ref "IC1") (pin "2") (pinfunction "PC13_2") (pintype "bidirectional"))
    )
    (net (code "69") (name "unconnected-(J2-Pad5)") (class "Default")
      (node (ref "J2") (pin "5") (pinfunction "5_5") (pintype "passive"))
    )
    (net (code "70") (name "unconnected-(U$4-Pad11)") (class "Default")
      (node (ref "U$4") (pin "11") (pinfunction "11_11") (pintype "bidirectional"))
    )
    (net (code "71") (name "unconnected-(U$4-Pad12)") (class "Default")
      (node (ref "U$4") (pin "12") (pinfunction "12_12") (pintype "bidirectional"))
    )
    (net (code "72") (name "unconnected-(U$4-Pad13)") (class "Default")
      (node (ref "U$4") (pin "13") (pinfunction "13_13") (pintype "bidirectional"))
    )
    (net (code "73") (name "unconnected-(U$4-Pad14)") (class "Default")
      (node (ref "U$4") (pin "14") (pinfunction "14_14") (pintype "bidirectional"))
    )
    (net (code "74") (name "unconnected-(U$4-Pad15)") (class "Default")
      (node (ref "U$4") (pin "15") (pinfunction "15_15") (pintype "bidirectional"))
    )
    (net (code "75") (name "unconnected-(U$4-Pad16)") (class "Default")
      (node (ref "U$4") (pin "16") (pinfunction "16_16") (pintype "bidirectional"))
    )
  )
)
